# 1_Power_Supply.net
KiCad netlist of a schematic drawn in Altium Designer
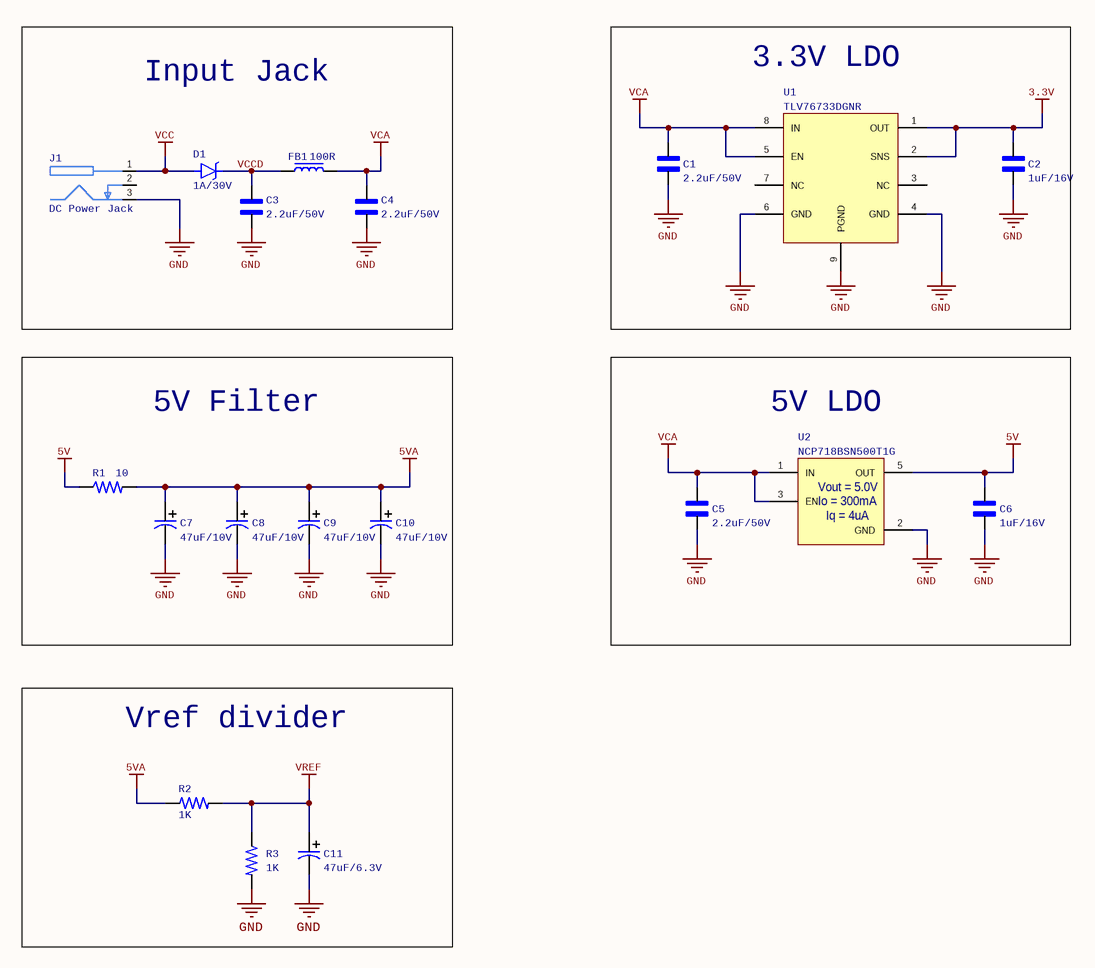
[diagram p0: [1] Power Supply.SchDoc]

(export (version "E")
  (design (tool "Eeschema 10.0.6"))
  (components
    (comp (ref "C1")
      (value "2.2uF/50V")
      (footprint "C1206")
      (description "MLCC 2.2uF 50V X7R 10% 1206")
      (fields
        (field (name "MANUFACTURER") "KEMET")
        (field (name "MANUFACTURER PART NUMBER") "C1206C225J5RECAUTO")
      )
      (libsource (lib "Capacitors") (part "C1206 2.2uF/50V"))
    )
    (comp (ref "C2")
      (value "1uF/16V")
      (footprint "C0603")
      (description "MLCC 1uF 16V X5R 10% SMD 0603 85C Paper T/R")
      (fields
        (field (name "MANUFACTURER") "Yageo")
        (field (name "MANUFACTURER PART NUMBER") "CC0603KRX5R7BB105")
      )
      (libsource (lib "Capacitors") (part "C0603 1uF/16V X5R"))
    )
    (comp (ref "C3")
      (value "2.2uF/50V")
      (footprint "C1206")
      (description "MLCC 2.2uF 50V X7R 10% 1206")
      (fields
        (field (name "MANUFACTURER") "KEMET")
        (field (name "MANUFACTURER PART NUMBER") "C1206C225J5RECAUTO")
      )
      (libsource (lib "Capacitors") (part "C1206 2.2uF/50V"))
    )
    (comp (ref "C4")
      (value "2.2uF/50V")
      (footprint "C1206")
      (description "MLCC 2.2uF 50V X7R 10% 1206")
      (fields
        (field (name "MANUFACTURER") "KEMET")
        (field (name "MANUFACTURER PART NUMBER") "C1206C225J5RECAUTO")
      )
      (libsource (lib "Capacitors") (part "C1206 2.2uF/50V"))
    )
    (comp (ref "C5")
      (value "2.2uF/50V")
      (footprint "C1206")
      (description "MLCC 2.2uF 50V X7R 10% 1206")
      (fields
        (field (name "MANUFACTURER") "KEMET")
        (field (name "MANUFACTURER PART NUMBER") "C1206C225J5RECAUTO")
      )
      (libsource (lib "Capacitors") (part "C1206 2.2uF/50V"))
    )
    (comp (ref "C6")
      (value "1uF/16V")
      (footprint "C0603")
      (description "MLCC 1uF 16V X5R 10% SMD 0603 85C Paper T/R")
      (fields
        (field (name "MANUFACTURER") "Yageo")
        (field (name "MANUFACTURER PART NUMBER") "CC0603KRX5R7BB105")
      )
      (libsource (lib "Capacitors") (part "C0603 1uF/16V X5R"))
    )
    (comp (ref "C7")
      (value "47uF/10V")
      (footprint "EIA1210")
      (description "Tantalum Capacitors - Solid SMD 10V 47uF 10%")
      (fields
        (field (name "MANUFACTURER") "Kyocera AVX")
        (field (name "MANUFACTURER PART NUMBER") "TAJB476K010RNJ")
      )
      (libsource (lib "Capacitors") (part "TANT 47UF/10V"))
    )
    (comp (ref "C8")
      (value "47uF/10V")
      (footprint "EIA1210")
      (description "Tantalum Capacitors - Solid SMD 10V 47uF 10%")
      (fields
        (field (name "MANUFACTURER") "Kyocera AVX")
        (field (name "MANUFACTURER PART NUMBER") "TAJB476K010RNJ")
      )
      (libsource (lib "Capacitors") (part "TANT 47UF/10V"))
    )
    (comp (ref "C9")
      (value "47uF/10V")
      (footprint "EIA1210")
      (description "Tantalum Capacitors - Solid SMD 10V 47uF 10%")
      (fields
        (field (name "MANUFACTURER") "Kyocera AVX")
        (field (name "MANUFACTURER PART NUMBER") "TAJB476K010RNJ")
      )
      (libsource (lib "Capacitors") (part "TANT 47UF/10V"))
    )
    (comp (ref "C10")
      (value "47uF/10V")
      (footprint "EIA1210")
      (description "Tantalum Capacitors - Solid SMD 10V 47uF 10%")
      (fields
        (field (name "MANUFACTURER") "Kyocera AVX")
        (field (name "MANUFACTURER PART NUMBER") "TAJB476K010RNJ")
      )
      (libsource (lib "Capacitors") (part "TANT 47UF/10V"))
    )
    (comp (ref "C11")
      (value "47uF/6.3V")
      (footprint "EIA1206")
      (description "Tantalum Capacitors - Solid SMD 6.3V 47uF 10%")
      (fields
        (field (name "MANUFACTURER") "Kyocera AVX")
        (field (name "MANUFACTURER PART NUMBER") "TAJA476K006SNJV")
      )
      (libsource (lib "Capacitors") (part "TANT 47UF/6.3V"))
    )
    (comp (ref "D1")
      (value "1A/30V")
      (footprint "SOD-323")
      (description "30V 1A SOD323 DIODE SCHOTTKY")
      (fields (field (name "MANUFACTURER") "Diodes") (field (name "MANUFACTURER PART NUMBER") "BAT760Q-7"))
      (libsource (lib "DiscreteSemi") (part "Schottky BAT760Q-7"))
    )
    (comp (ref "FB1")
      (value "100R")
      (footprint "FB_0603")
      (description "Ferrite Bead SMD 0603")
      (libsource (lib "Schematic-Lib-PhilsLab") (part "FB_0603"))
    )
    (comp (ref "J1")
      (value "DC Power Jack")
      (footprint "DC Power Jack 2.1mm x 5.5mm")
      (description "DC Power Connectors Power Jack/Connector 2.1mm x 5.5mm")
      (fields
        (field (name "MANUFACTURER") "Gravitech")
        (field (name "MANUFACTURER PART NUMBER") "CON-SOCJ-2155")
      )
      (libsource (lib "Connectors") (part "DC Power Jack 2.1mm x 5.5mm"))
    )
    (comp (ref "R1")
      (value "10")
      (footprint "R0603")
      (description "RES 0603 10 OHM 0.5% 1/10W")
      (fields
        (field (name "MANUFACTURER") "Yageo")
        (field (name "MANUFACTURER PART NUMBER") "RT0603DRE0710RL")
      )
      (libsource (lib "Resistors") (part "R0603 10"))
    )
    (comp (ref "R2")
      (value "1K")
      (footprint "R0603")
      (description "Res Thick Film 0603 1K Ohm 1% 1/10W ±50ppm/°C Molded SMD Paper T/R")
      (fields
        (field (name "MANUFACTURER") "Yageo")
        (field (name "MANUFACTURER PART NUMBER") "RE0603FRE071KL")
      )
      (libsource (lib "Resistors") (part "R0603 1K"))
    )
    (comp (ref "R3")
      (value "1K")
      (footprint "R0603")
      (description "Res Thick Film 0603 1K Ohm 1% 1/10W ±50ppm/°C Molded SMD Paper T/R")
      (fields
        (field (name "MANUFACTURER") "Yageo")
        (field (name "MANUFACTURER PART NUMBER") "RE0603FRE071KL")
      )
      (libsource (lib "Resistors") (part "R0603 1K"))
    )
    (comp (ref "U1")
      (value "TLV76733DGNR")
      (footprint "HVSSOP-8")
      (description "Fixed-output, 1-A, 16-V, positive-voltage low-dropout (LDO) linear regulator 8-HVSSOP -40 to 125")
      (fields (field (name "MANUFACTURER") "Texas Instruments"))
      (libsource (lib "IC Power") (part "TLV76733DGNR"))
    )
    (comp (ref "U2")
      (value "NCP718BSN500T1G")
      (footprint "SOT23-5")
      (description "LDO Regulator, 300 mA, Wide Vin, Ultra-Low Iq Fixed 5.0V, Non-Active Discharge, TSOT23-5")
      (fields (field (name "MANUFACTURER") "ON Semiconductor"))
      (libsource (lib "IC Power") (part "NCP718BSN500T1G"))
    )
  )
  (nets
    (net (code "1") (name "/VCCD") (class "Default")
      (node (ref "C3") (pin "1") (pinfunction "1_1") (pintype "passive"))
      (node (ref "D1") (pin "C") (pinfunction "C_C") (pintype "passive"))
      (node (ref "FB1") (pin "1") (pinfunction "1_1") (pintype "passive"))
    )
    (net (code "2") (name "3.3V") (class "Default")
      (node (ref "C2") (pin "1") (pinfunction "1_1") (pintype "passive"))
      (node (ref "U1") (pin "1") (pinfunction "OUT_1") (pintype "passive"))
      (node (ref "U1") (pin "2") (pinfunction "SNS_2") (pintype "passive"))
    )
    (net (code "3") (name "5V") (class "Default")
      (node (ref "C6") (pin "1") (pinfunction "1_1") (pintype "passive"))
      (node (ref "R1") (pin "1") (pinfunction "1_1") (pintype "passive"))
      (node (ref "U2") (pin "5") (pinfunction "OUT_5") (pintype "power_in"))
    )
    (net (code "4") (name "5VA") (class "Default")
      (node (ref "C10") (pin "1") (pinfunction "1_1") (pintype "passive"))
      (node (ref "C7") (pin "1") (pinfunction "1_1") (pintype "passive"))
      (node (ref "C8") (pin "1") (pinfunction "1_1") (pintype "passive"))
      (node (ref "C9") (pin "1") (pinfunction "1_1") (pintype "passive"))
      (node (ref "R1") (pin "2") (pinfunction "2_2") (pintype "passive"))
      (node (ref "R2") (pin "1") (pinfunction "1_1") (pintype "passive"))
    )
    (net (code "5") (name "GND") (class "Default")
      (node (ref "C1") (pin "2") (pinfunction "2_2") (pintype "passive"))
      (node (ref "C10") (pin "2") (pinfunction "2_2") (pintype "passive"))
      (node (ref "C11") (pin "2") (pinfunction "2_2") (pintype "passive"))
      (node (ref "C2") (pin "2") (pinfunction "2_2") (pintype "passive"))
      (node (ref "C3") (pin "2") (pinfunction "2_2") (pintype "passive"))
      (node (ref "C4") (pin "2") (pinfunction "2_2") (pintype "passive"))
      (node (ref "C5") (pin "2") (pinfunction "2_2") (pintype "passive"))
      (node (ref "C6") (pin "2") (pinfunction "2_2") (pintype "passive"))
      (node (ref "C7") (pin "2") (pinfunction "2_2") (pintype "passive"))
      (node (ref "C8") (pin "2") (pinfunction "2_2") (pintype "passive"))
      (node (ref "C9") (pin "2") (pinfunction "2_2") (pintype "passive"))
      (node (ref "J1") (pin "3") (pinfunction "3_3") (pintype "passive"))
      (node (ref "R3") (pin "2") (pinfunction "2_2") (pintype "passive"))
      (node (ref "U1") (pin "4") (pinfunction "GND_4") (pintype "passive"))
      (node (ref "U1") (pin "6") (pinfunction "GND_6") (pintype "passive"))
      (node (ref "U1") (pin "9") (pinfunction "PGND_9") (pintype "passive"))
      (node (ref "U2") (pin "2") (pinfunction "GND_2") (pintype "power_in"))
    )
    (net (code "6") (name "VCA") (class "Default")
      (node (ref "C1") (pin "1") (pinfunction "1_1") (pintype "passive"))
      (node (ref "C4") (pin "1") (pinfunction "1_1") (pintype "passive"))
      (node (ref "C5") (pin "1") (pinfunction "1_1") (pintype "passive"))
      (node (ref "FB1") (pin "2") (pinfunction "2_2") (pintype "passive"))
      (node (ref "U1") (pin "5") (pinfunction "EN_5") (pintype "passive"))
      (node (ref "U1") (pin "8") (pinfunction "IN_8") (pintype "passive"))
      (node (ref "U2") (pin "1") (pinfunction "IN_1") (pintype "power_in"))
      (node (ref "U2") (pin "3") (pinfunction "EN_3") (pintype "passive"))
    )
    (net (code "7") (name "VCC") (class "Default")
      (node (ref "D1") (pin "A") (pinfunction "A_A") (pintype "passive"))
      (node (ref "J1") (pin "1") (pinfunction "1_1") (pintype "passive"))
    )
    (net (code "8") (name "VREF") (class "Default")
      (node (ref "C11") (pin "1") (pinfunction "1_1") (pintype "passive"))
      (node (ref "R2") (pin "2") (pinfunction "2_2") (pintype "passive"))
      (node (ref "R3") (pin "1") (pinfunction "1_1") (pintype "passive"))
    )
    (net (code "9") (name "unconnected-(J1-Pad2)") (class "Default")
      (node (ref "J1") (pin "2") (pinfunction "2_2") (pintype "passive"))
    )
    (net (code "10") (name "unconnected-(U1-NC-Pad3)") (class "Default")
      (node (ref "U1") (pin "3") (pinfunction "NC_3") (pintype "passive"))
    )
    (net (code "11") (name "unconnected-(U1-NC-Pad7)") (class "Default")
      (node (ref "U1") (pin "7") (pinfunction "NC_7") (pintype "passive"))
    )
  )
)
